# 5V-Switcher.net
KiCad netlist of a schematic drawn in Altium Designer
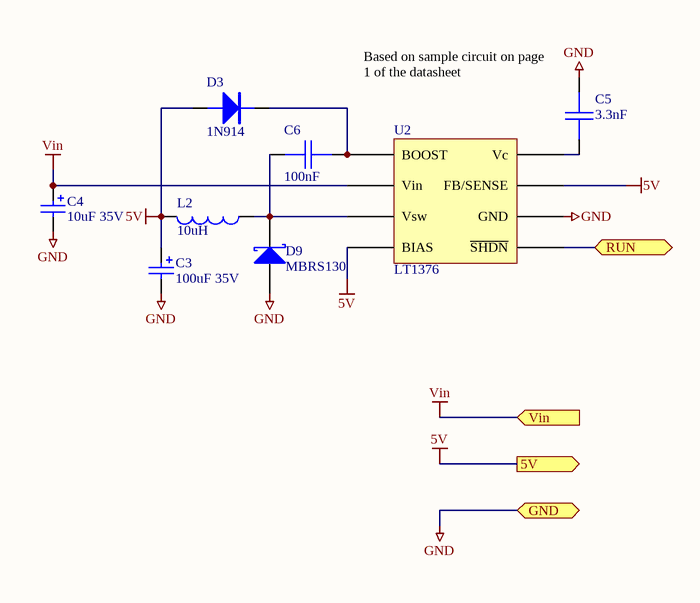
[diagram p0: 5V-Switcher.SchDoc]

(export (version "E")
  (design (tool "Eeschema 10.0.6"))
  (components
    (comp (ref "C3")
      (value "100uF 35V")
      (footprint "MCCT-CASEC")
      (description "Polarized Capacitor (Surface Mount)")
      (libsource (lib "Miscellaneous Devices") (part "Cap Pol3"))
    )
    (comp (ref "C4")
      (value "10uF 35V")
      (footprint "MCCT-CASEC")
      (description "Polarized Capacitor (Surface Mount)")
      (libsource (lib "Miscellaneous Devices") (part "Cap Pol3"))
    )
    (comp (ref "C5")
      (value "3.3nF")
      (footprint "0603")
      (description "Capacitor")
      (libsource (lib "Miscellaneous Devices") (part "CAP"))
    )
    (comp (ref "C6")
      (value "100nF")
      (footprint "0603")
      (description "Capacitor")
      (libsource (lib "Miscellaneous Devices") (part "CAP"))
    )
    (comp (ref "D3")
      (value "1N914")
      (footprint "SMB")
      (description "Diode")
      (libsource (lib "2009_BatteryMaster") (part "DIODE"))
    )
    (comp (ref "D9")
      (value "MBRS130")
      (footprint "SMB")
      (description "Schottky Diode")
      (libsource (lib "RCLDQ") (part "D SCHOTTKY"))
    )
    (comp (ref "L2")
      (value "10uH")
      (footprint "1812")
      (description "Inductor")
      (libsource (lib "Miscellaneous Devices") (part "Inductor"))
    )
    (comp (ref "U2") (value "LT1376") (footprint "SO8") (libsource (lib "BMS") (part "LT1376")))
  )
  (nets
    (net (code "1") (name "/RUN") (class "Default")
      (node (ref "U2") (pin "5") (pinfunction "~{SHDN}_5") (pintype "passive"))
    )
    (net (code "2") (name "5V") (class "Default")
      (node (ref "C3") (pin "1") (pinfunction "1_1") (pintype "passive"))
      (node (ref "D3") (pin "A") (pinfunction "A_A") (pintype "passive"))
      (node (ref "L2") (pin "2") (pinfunction "2_2") (pintype "passive"))
      (node (ref "U2") (pin "4") (pinfunction "BIAS_4") (pintype "passive"))
      (node (ref "U2") (pin "7") (pinfunction "FB/SENSE_7") (pintype "passive"))
    )
    (net (code "3") (name "GND") (class "Default")
      (node (ref "C3") (pin "2") (pinfunction "2_2") (pintype "passive"))
      (node (ref "C4") (pin "2") (pinfunction "2_2") (pintype "passive"))
      (node (ref "C5") (pin "1") (pinfunction "1_1") (pintype "passive"))
      (node (ref "D9") (pin "A") (pinfunction "A_A") (pintype "passive"))
      (node (ref "U2") (pin "6") (pinfunction "GND_6") (pintype "passive"))
    )
    (net (code "4") (name "Net-(U2-BOOST)") (class "Default")
      (node (ref "C6") (pin "2") (pinfunction "2_2") (pintype "passive"))
      (node (ref "D3") (pin "K") (pinfunction "K_K") (pintype "passive"))
      (node (ref "U2") (pin "1") (pinfunction "BOOST_1") (pintype "passive"))
    )
    (net (code "5") (name "Net-(U2-Vc)") (class "Default")
      (node (ref "C5") (pin "2") (pinfunction "2_2") (pintype "passive"))
      (node (ref "U2") (pin "8") (pinfunction "Vc_8") (pintype "passive"))
    )
    (net (code "6") (name "Net-(U2-Vsw)") (class "Default")
      (node (ref "C6") (pin "1") (pinfunction "1_1") (pintype "passive"))
      (node (ref "D9") (pin "K") (pinfunction "K_K") (pintype "passive"))
      (node (ref "L2") (pin "1") (pinfunction "1_1") (pintype "passive"))
      (node (ref "U2") (pin "3") (pinfunction "Vsw_3") (pintype "passive"))
    )
    (net (code "7") (name "Vin") (class "Default")
      (node (ref "C4") (pin "1") (pinfunction "1_1") (pintype "passive"))
      (node (ref "U2") (pin "2") (pinfunction "Vin_2") (pintype "passive"))
    )
  )
)
